# I2C_WAV_HalfShield.net
KiCad netlist of a schematic drawn in EAGLE
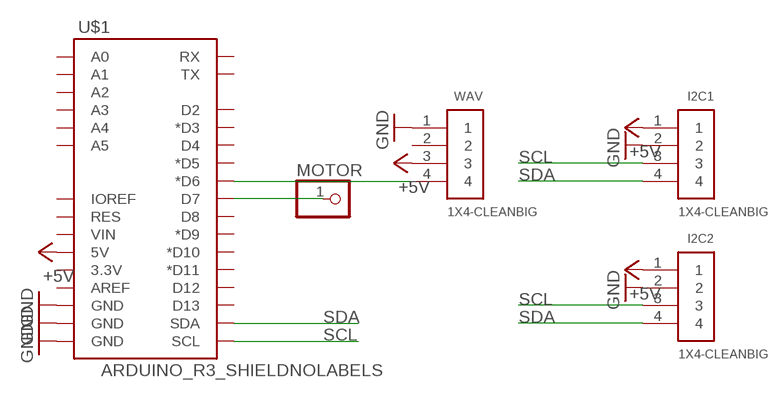
[diagram p0: schematic, sheet 1]

(export (version "E")
  (design (tool "Eeschema 10.0.6"))
  (components
    (comp (ref "I2C1")
      (value "1X4-CLEANBIG")
      (footprint "eagle-import:1X04-CLEANBIG")
      (libsource (lib "eagle-import") (part "1X4-CLEANBIG"))
    )
    (comp (ref "I2C2")
      (value "1X4-CLEANBIG")
      (footprint "eagle-import:1X04-CLEANBIG")
      (libsource (lib "eagle-import") (part "1X4-CLEANBIG"))
    )
    (comp (ref "MOTOR")
      (value "PINHD-1X1CB")
      (footprint "eagle-import:1X01-CLEANBIG")
      (libsource (lib "eagle-import") (part "PINHD-1X1CB"))
    )
    (comp (ref "U$1")
      (value "ARDUINO_R3_SHIELDNOLABELS")
      (footprint "eagle-import:UNO_R3_SHIELD_NOLABELS")
      (libsource (lib "eagle-import") (part "ARDUINO_R3_SHIELDNOLABELS"))
    )
    (comp (ref "WAV")
      (value "1X4-CLEANBIG")
      (footprint "eagle-import:1X04-CLEANBIG")
      (libsource (lib "eagle-import") (part "1X4-CLEANBIG"))
    )
  )
  (nets
    (net (code "1") (name "+5V") (class "Default")
      (node (ref "I2C1") (pin "1") (pinfunction "1_1") (pintype "bidirectional"))
      (node (ref "I2C2") (pin "1") (pinfunction "1_1") (pintype "bidirectional"))
      (node (ref "U$1") (pin "5V") (pinfunction "5V_5V") (pintype "bidirectional"))
      (node (ref "WAV") (pin "3") (pinfunction "3_3") (pintype "bidirectional"))
    )
    (net (code "2") (name "/SCL") (class "Default")
      (node (ref "I2C1") (pin "3") (pinfunction "3_3") (pintype "bidirectional"))
      (node (ref "I2C2") (pin "3") (pinfunction "3_3") (pintype "bidirectional"))
      (node (ref "U$1") (pin "SCL") (pinfunction "SCL_SCL") (pintype "bidirectional"))
    )
    (net (code "3") (name "/SDA") (class "Default")
      (node (ref "I2C1") (pin "4") (pinfunction "4_4") (pintype "bidirectional"))
      (node (ref "I2C2") (pin "4") (pinfunction "4_4") (pintype "bidirectional"))
      (node (ref "U$1") (pin "SDA") (pinfunction "SDA_SDA") (pintype "bidirectional"))
    )
    (net (code "4") (name "GND") (class "Default")
      (node (ref "I2C1") (pin "2") (pinfunction "2_2") (pintype "bidirectional"))
      (node (ref "I2C2") (pin "2") (pinfunction "2_2") (pintype "bidirectional"))
      (node (ref "U$1") (pin "GND@0") (pinfunction "GND_GND@0") (pintype "bidirectional"))
      (node (ref "U$1") (pin "GND@1") (pinfunction "GND_GND@1") (pintype "bidirectional"))
      (node (ref "U$1") (pin "GND@2") (pinfunction "GND_GND@2") (pintype "bidirectional"))
      (node (ref "WAV") (pin "1") (pinfunction "1_1") (pintype "bidirectional"))
    )
    (net (code "5") (name "Net-(MOTOR-Pad1)") (class "Default")
      (node (ref "MOTOR") (pin "1") (pinfunction "1_1") (pintype "passive"))
      (node (ref "U$1") (pin "D7") (pinfunction "D7_D7") (pintype "bidirectional"))
    )
    (net (code "6") (name "Net-(U$1-*D6)") (class "Default")
      (node (ref "U$1") (pin "D6") (pinfunction "*D6_D6") (pintype "bidirectional"))
      (node (ref "WAV") (pin "4") (pinfunction "4_4") (pintype "bidirectional"))
    )
    (net (code "7") (name "unconnected-(U$1-*D3-PadD3)") (class "Default")
      (node (ref "U$1") (pin "D3") (pinfunction "*D3_D3") (pintype "bidirectional"))
    )
    (net (code "8") (name "unconnected-(U$1-*D5-PadD5)") (class "Default")
      (node (ref "U$1") (pin "D5") (pinfunction "*D5_D5") (pintype "bidirectional"))
    )
    (net (code "9") (name "unconnected-(U$1-*D9-PadD9)") (class "Default")
      (node (ref "U$1") (pin "D9") (pinfunction "*D9_D9") (pintype "bidirectional"))
    )
    (net (code "10") (name "unconnected-(U$1-*D10-PadD10)") (class "Default")
      (node (ref "U$1") (pin "D10") (pinfunction "*D10_D10") (pintype "bidirectional"))
    )
    (net (code "11") (name "unconnected-(U$1-*D11-PadD11)") (class "Default")
      (node (ref "U$1") (pin "D11") (pinfunction "*D11_D11") (pintype "bidirectional"))
    )
    (net (code "12") (name "unconnected-(U$1-Pad3.3V)") (class "Default")
      (node (ref "U$1") (pin "3.3V") (pinfunction "3.3V_3.3V") (pintype "bidirectional"))
    )
    (net (code "13") (name "unconnected-(U$1-PadA0)") (class "Default")
      (node (ref "U$1") (pin "A0") (pinfunction "A0_A0") (pintype "bidirectional"))
    )
    (net (code "14") (name "unconnected-(U$1-PadA1)") (class "Default")
      (node (ref "U$1") (pin "A1") (pinfunction "A1_A1") (pintype "bidirectional"))
    )
    (net (code "15") (name "unconnected-(U$1-PadA2)") (class "Default")
      (node (ref "U$1") (pin "A2") (pinfunction "A2_A2") (pintype "bidirectional"))
    )
    (net (code "16") (name "unconnected-(U$1-PadA3)") (class "Default")
      (node (ref "U$1") (pin "A3") (pinfunction "A3_A3") (pintype "bidirectional"))
    )
    (net (code "17") (name "unconnected-(U$1-PadA4)") (class "Default")
      (node (ref "U$1") (pin "A4") (pinfunction "A4_A4") (pintype "bidirectional"))
    )
    (net (code "18") (name "unconnected-(U$1-PadA5)") (class "Default")
      (node (ref "U$1") (pin "A5") (pinfunction "A5_A5") (pintype "bidirectional"))
    )
    (net (code "19") (name "unconnected-(U$1-PadAREF)") (class "Default")
      (node (ref "U$1") (pin "AREF") (pinfunction "AREF_AREF") (pintype "bidirectional"))
    )
    (net (code "20") (name "unconnected-(U$1-PadD2)") (class "Default")
      (node (ref "U$1") (pin "D2") (pinfunction "D2_D2") (pintype "bidirectional"))
    )
    (net (code "21") (name "unconnected-(U$1-PadD4)") (class "Default")
      (node (ref "U$1") (pin "D4") (pinfunction "D4_D4") (pintype "bidirectional"))
    )
    (net (code "22") (name "unconnected-(U$1-PadD8)") (class "Default")
      (node (ref "U$1") (pin "D8") (pinfunction "D8_D8") (pintype "bidirectional"))
    )
    (net (code "23") (name "unconnected-(U$1-PadD12)") (class "Default")
      (node (ref "U$1") (pin "D12") (pinfunction "D12_D12") (pintype "bidirectional"))
    )
    (net (code "24") (name "unconnected-(U$1-PadD13)") (class "Default")
      (node (ref "U$1") (pin "D13") (pinfunction "D13_D13") (pintype "bidirectional"))
    )
    (net (code "25") (name "unconnected-(U$1-PadIOREF)") (class "Default")
      (node (ref "U$1") (pin "IOREF") (pinfunction "IOREF_IOREF") (pintype "bidirectional"))
    )
    (net (code "26") (name "unconnected-(U$1-PadRES)") (class "Default")
      (node (ref "U$1") (pin "RES") (pinfunction "RES_RES") (pintype "bidirectional"))
    )
    (net (code "27") (name "unconnected-(U$1-PadRX)") (class "Default")
      (node (ref "U$1") (pin "RX") (pinfunction "RX_RX") (pintype "bidirectional"))
    )
    (net (code "28") (name "unconnected-(U$1-PadTX)") (class "Default")
      (node (ref "U$1") (pin "TX") (pinfunction "TX_TX") (pintype "bidirectional"))
    )
    (net (code "29") (name "unconnected-(U$1-PadVIN)") (class "Default")
      (node (ref "U$1") (pin "VIN") (pinfunction "VIN_VIN") (pintype "bidirectional"))
    )
    (net (code "30") (name "unconnected-(WAV-Pad2)") (class "Default")
      (node (ref "WAV") (pin "2") (pinfunction "2_2") (pintype "bidirectional"))
    )
  )
)
